# shield_passage_vitesse.net
KiCad netlist of a schematic drawn in EAGLE
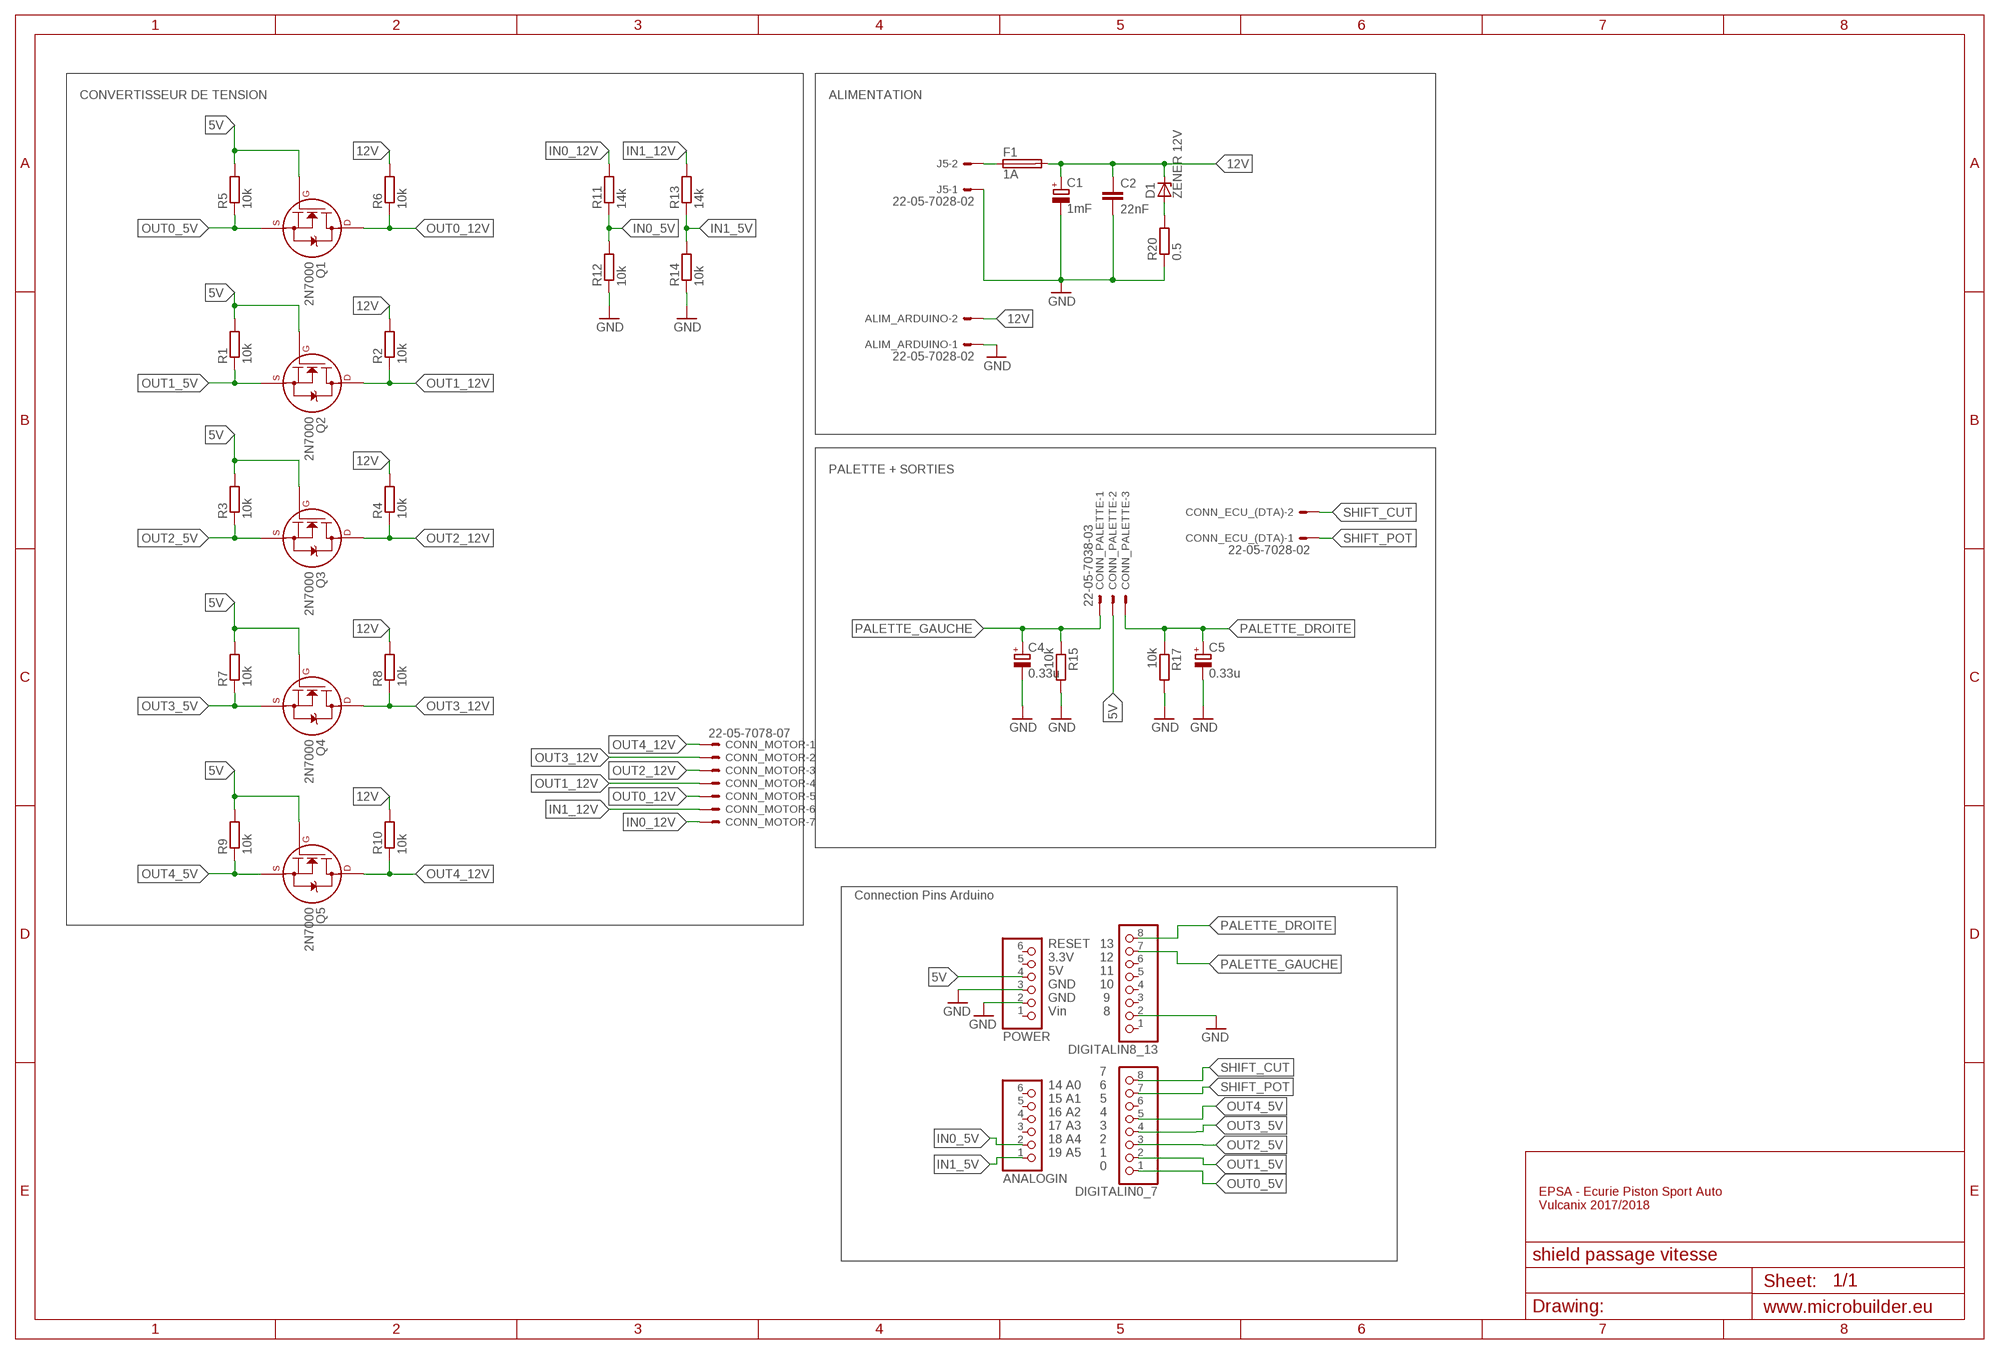
[diagram p0: schematic, sheet 1]

(export (version "E")
  (design (tool "Eeschema 10.0.6"))
  (components
    (comp (ref "ALIM_ARDUINO")
      (value "22-05-7028-02")
      (footprint "eagle-import:7395-02")
      (libsource (lib "eagle-import") (part "22-?-0205-7028"))
    )
    (comp (ref "ANALOGIN")
      (value "PINHD-1X6CB")
      (footprint "eagle-import:1X06-CLEANBIG")
      (libsource (lib "eagle-import") (part "PINHD-1X6CB"))
    )
    (comp (ref "C1")
      (value "1mF")
      (footprint "eagle-import:E7,5-16")
      (libsource (lib "eagle-import") (part "rcl_334_CPOL-EUE7.5-16"))
    )
    (comp (ref "C2")
      (value "22nF")
      (footprint "eagle-import:C025-025X050")
      (libsource (lib "eagle-import") (part "C-EU025-025X050"))
    )
    (comp (ref "C4")
      (value "0.33u")
      (footprint "eagle-import:E2,5-6E")
      (libsource (lib "eagle-import") (part "CPOL-EUE2,5-6E"))
    )
    (comp (ref "C5")
      (value "0.33u")
      (footprint "eagle-import:E2,5-6E")
      (libsource (lib "eagle-import") (part "CPOL-EUE2,5-6E"))
    )
    (comp (ref "CONN_ECU_(DTA)")
      (value "22-05-7028-02")
      (footprint "eagle-import:7395-02")
      (libsource (lib "eagle-import") (part "22-?-0205-7028"))
    )
    (comp (ref "CONN_MOTOR")
      (value "22-05-7078-07")
      (footprint "eagle-import:7395-07")
      (libsource (lib "eagle-import") (part "22-?-0705-7078"))
    )
    (comp (ref "CONN_PALETTE")
      (value "22-05-7038-03")
      (footprint "eagle-import:7395-03")
      (libsource (lib "eagle-import") (part "22-?-0305-7038"))
    )
    (comp (ref "D1")
      (value "ZENER 12V")
      (footprint "eagle-import:DO41Z10")
      (libsource (lib "eagle-import") (part "ZENER-DIODEDO41Z10"))
    )
    (comp (ref "DIGITALIN0_7")
      (value "PINHD-1X8CLEANBIG")
      (footprint "eagle-import:1X08-CLEANBIG")
      (libsource (lib "eagle-import") (part "PINHD-1X8CLEANBIG"))
    )
    (comp (ref "DIGITALIN8_13")
      (value "PINHD-1X8CLEANBIG")
      (footprint "eagle-import:1X08-CLEANBIG")
      (libsource (lib "eagle-import") (part "PINHD-1X8CLEANBIG"))
    )
    (comp (ref "F1")
      (value "1A")
      (footprint "eagle-import:SH25")
      (fields (field (name "MF") "SCHURTER") (field (name "MPN") "0031.8211"))
      (libsource (lib "eagle-import") (part "SH25"))
    )
    (comp (ref "J5")
      (value "22-05-7028-02")
      (footprint "eagle-import:7395-02")
      (libsource (lib "eagle-import") (part "22-?-0205-7028"))
    )
    (comp (ref "POWER")
      (value "PINHD-1X6CB")
      (footprint "eagle-import:1X06-CLEANBIG")
      (libsource (lib "eagle-import") (part "PINHD-1X6CB"))
    )
    (comp (ref "Q1")
      (value "2N7000")
      (footprint "eagle-import:TO-92")
      (libsource (lib "eagle-import") (part "2N700_TO920"))
    )
    (comp (ref "Q2")
      (value "2N7000")
      (footprint "eagle-import:TO-92")
      (libsource (lib "eagle-import") (part "2N700_TO920"))
    )
    (comp (ref "Q3")
      (value "2N7000")
      (footprint "eagle-import:TO-92")
      (libsource (lib "eagle-import") (part "2N700_TO920"))
    )
    (comp (ref "Q4")
      (value "2N7000")
      (footprint "eagle-import:TO-92")
      (libsource (lib "eagle-import") (part "2N700_TO920"))
    )
    (comp (ref "Q5")
      (value "2N7000")
      (footprint "eagle-import:TO-92")
      (libsource (lib "eagle-import") (part "2N700_TO920"))
    )
    (comp (ref "R1")
      (value "10k")
      (footprint "eagle-import:0204_7")
      (libsource (lib "eagle-import") (part "R-EU_0204/7"))
    )
    (comp (ref "R2")
      (value "10k")
      (footprint "eagle-import:0204_7")
      (libsource (lib "eagle-import") (part "R-EU_0204/7"))
    )
    (comp (ref "R3")
      (value "10k")
      (footprint "eagle-import:0204_7")
      (libsource (lib "eagle-import") (part "R-EU_0204/7"))
    )
    (comp (ref "R4")
      (value "10k")
      (footprint "eagle-import:0204_7")
      (libsource (lib "eagle-import") (part "R-EU_0204/7"))
    )
    (comp (ref "R5")
      (value "10k")
      (footprint "eagle-import:0204_7")
      (libsource (lib "eagle-import") (part "R-EU_0204/7"))
    )
    (comp (ref "R6")
      (value "10k")
      (footprint "eagle-import:0204_7")
      (libsource (lib "eagle-import") (part "R-EU_0204/7"))
    )
    (comp (ref "R7")
      (value "10k")
      (footprint "eagle-import:0204_7")
      (libsource (lib "eagle-import") (part "R-EU_0204/7"))
    )
    (comp (ref "R8")
      (value "10k")
      (footprint "eagle-import:0204_7")
      (libsource (lib "eagle-import") (part "R-EU_0204/7"))
    )
    (comp (ref "R9")
      (value "10k")
      (footprint "eagle-import:0204_7")
      (libsource (lib "eagle-import") (part "R-EU_0204/7"))
    )
    (comp (ref "R10")
      (value "10k")
      (footprint "eagle-import:0204_7")
      (libsource (lib "eagle-import") (part "R-EU_0204/7"))
    )
    (comp (ref "R11")
      (value "14k")
      (footprint "eagle-import:0204_7")
      (libsource (lib "eagle-import") (part "R-EU_0204/7"))
    )
    (comp (ref "R12")
      (value "10k")
      (footprint "eagle-import:0204_7")
      (libsource (lib "eagle-import") (part "R-EU_0204/7"))
    )
    (comp (ref "R13")
      (value "14k")
      (footprint "eagle-import:0204_7")
      (libsource (lib "eagle-import") (part "R-EU_0204/7"))
    )
    (comp (ref "R14")
      (value "10k")
      (footprint "eagle-import:0204_7")
      (libsource (lib "eagle-import") (part "R-EU_0204/7"))
    )
    (comp (ref "R15")
      (value "10k")
      (footprint "eagle-import:0204_7")
      (libsource (lib "eagle-import") (part "R-EU_0204/7"))
    )
    (comp (ref "R17")
      (value "10k")
      (footprint "eagle-import:0204_7")
      (libsource (lib "eagle-import") (part "R-EU_0204/7"))
    )
    (comp (ref "R20")
      (value "0.5")
      (footprint "eagle-import:0309_12")
      (libsource (lib "eagle-import") (part "R-EU_0309/12"))
    )
  )
  (nets
    (net (code "1") (name "5V") (class "Default")
      (node (ref "CONN_PALETTE") (pin "2") (pinfunction "S_2") (pintype "passive"))
      (node (ref "POWER") (pin "4") (pinfunction "4_4") (pintype "passive"))
      (node (ref "Q1") (pin "2") (pinfunction "G_2") (pintype "tri_state"))
      (node (ref "Q2") (pin "2") (pinfunction "G_2") (pintype "tri_state"))
      (node (ref "Q3") (pin "2") (pinfunction "G_2") (pintype "tri_state"))
      (node (ref "Q4") (pin "2") (pinfunction "G_2") (pintype "tri_state"))
      (node (ref "Q5") (pin "2") (pinfunction "G_2") (pintype "tri_state"))
      (node (ref "R1") (pin "2") (pinfunction "2_2") (pintype "passive"))
      (node (ref "R3") (pin "2") (pinfunction "2_2") (pintype "passive"))
      (node (ref "R5") (pin "2") (pinfunction "2_2") (pintype "passive"))
      (node (ref "R7") (pin "2") (pinfunction "2_2") (pintype "passive"))
      (node (ref "R9") (pin "2") (pinfunction "2_2") (pintype "passive"))
    )
    (net (code "2") (name "12V") (class "Default")
      (node (ref "ALIM_ARDUINO") (pin "2") (pinfunction "S_2") (pintype "passive"))
      (node (ref "C1") (pin "+") (pinfunction "+_+") (pintype "passive"))
      (node (ref "C2") (pin "1") (pinfunction "1_1") (pintype "passive"))
      (node (ref "D1") (pin "C") (pinfunction "C_C") (pintype "passive"))
      (node (ref "F1") (pin "2") (pinfunction "2_2") (pintype "passive"))
      (node (ref "R10") (pin "2") (pinfunction "2_2") (pintype "passive"))
      (node (ref "R2") (pin "2") (pinfunction "2_2") (pintype "passive"))
      (node (ref "R4") (pin "2") (pinfunction "2_2") (pintype "passive"))
      (node (ref "R6") (pin "2") (pinfunction "2_2") (pintype "passive"))
      (node (ref "R8") (pin "2") (pinfunction "2_2") (pintype "passive"))
    )
    (net (code "3") (name "GND") (class "Default")
      (node (ref "ALIM_ARDUINO") (pin "1") (pinfunction "S_1") (pintype "passive"))
      (node (ref "C1") (pin "-") (pinfunction "-_-") (pintype "passive"))
      (node (ref "C2") (pin "2") (pinfunction "2_2") (pintype "passive"))
      (node (ref "C4") (pin "-") (pinfunction "-_-") (pintype "passive"))
      (node (ref "C5") (pin "-") (pinfunction "-_-") (pintype "passive"))
      (node (ref "DIGITALIN8_13") (pin "2") (pinfunction "2_2") (pintype "passive"))
      (node (ref "J5") (pin "1") (pinfunction "S_1") (pintype "passive"))
      (node (ref "POWER") (pin "2") (pinfunction "2_2") (pintype "passive"))
      (node (ref "POWER") (pin "3") (pinfunction "3_3") (pintype "passive"))
      (node (ref "R12") (pin "1") (pinfunction "1_1") (pintype "passive"))
      (node (ref "R14") (pin "1") (pinfunction "1_1") (pintype "passive"))
      (node (ref "R15") (pin "2") (pinfunction "2_2") (pintype "passive"))
      (node (ref "R17") (pin "2") (pinfunction "2_2") (pintype "passive"))
      (node (ref "R20") (pin "1") (pinfunction "1_1") (pintype "passive"))
    )
    (net (code "4") (name "IN0_5V") (class "Default")
      (node (ref "ANALOGIN") (pin "2") (pinfunction "2_2") (pintype "passive"))
      (node (ref "R11") (pin "1") (pinfunction "1_1") (pintype "passive"))
      (node (ref "R12") (pin "2") (pinfunction "2_2") (pintype "passive"))
    )
    (net (code "5") (name "IN0_12V") (class "Default")
      (node (ref "CONN_MOTOR") (pin "7") (pinfunction "S_7") (pintype "passive"))
      (node (ref "R11") (pin "2") (pinfunction "2_2") (pintype "passive"))
    )
    (net (code "6") (name "IN1_5V") (class "Default")
      (node (ref "ANALOGIN") (pin "1") (pinfunction "1_1") (pintype "passive"))
      (node (ref "R13") (pin "1") (pinfunction "1_1") (pintype "passive"))
      (node (ref "R14") (pin "2") (pinfunction "2_2") (pintype "passive"))
    )
    (net (code "7") (name "IN1_12V") (class "Default")
      (node (ref "CONN_MOTOR") (pin "6") (pinfunction "S_6") (pintype "passive"))
      (node (ref "R13") (pin "2") (pinfunction "2_2") (pintype "passive"))
    )
    (net (code "8") (name "Net-(D1-PadA)") (class "Default")
      (node (ref "D1") (pin "A") (pinfunction "A_A") (pintype "passive"))
      (node (ref "R20") (pin "2") (pinfunction "2_2") (pintype "passive"))
    )
    (net (code "9") (name "Net-(J5B-S)") (class "Default")
      (node (ref "F1") (pin "1") (pinfunction "1_1") (pintype "passive"))
      (node (ref "J5") (pin "2") (pinfunction "S_2") (pintype "passive"))
    )
    (net (code "10") (name "OUT0_5V") (class "Default")
      (node (ref "DIGITALIN0_7") (pin "1") (pinfunction "1_1") (pintype "passive"))
      (node (ref "Q1") (pin "1") (pinfunction "S_1") (pintype "bidirectional"))
      (node (ref "R5") (pin "1") (pinfunction "1_1") (pintype "passive"))
    )
    (net (code "11") (name "OUT0_12V") (class "Default")
      (node (ref "CONN_MOTOR") (pin "5") (pinfunction "S_5") (pintype "passive"))
      (node (ref "Q1") (pin "3") (pinfunction "D_3") (pintype "bidirectional"))
      (node (ref "R6") (pin "1") (pinfunction "1_1") (pintype "passive"))
    )
    (net (code "12") (name "OUT1_5V") (class "Default")
      (node (ref "DIGITALIN0_7") (pin "2") (pinfunction "2_2") (pintype "passive"))
      (node (ref "Q2") (pin "1") (pinfunction "S_1") (pintype "bidirectional"))
      (node (ref "R1") (pin "1") (pinfunction "1_1") (pintype "passive"))
    )
    (net (code "13") (name "OUT1_12V") (class "Default")
      (node (ref "CONN_MOTOR") (pin "4") (pinfunction "S_4") (pintype "passive"))
      (node (ref "Q2") (pin "3") (pinfunction "D_3") (pintype "bidirectional"))
      (node (ref "R2") (pin "1") (pinfunction "1_1") (pintype "passive"))
    )
    (net (code "14") (name "OUT2_5V") (class "Default")
      (node (ref "DIGITALIN0_7") (pin "3") (pinfunction "3_3") (pintype "passive"))
      (node (ref "Q3") (pin "1") (pinfunction "S_1") (pintype "bidirectional"))
      (node (ref "R3") (pin "1") (pinfunction "1_1") (pintype "passive"))
    )
    (net (code "15") (name "OUT2_12V") (class "Default")
      (node (ref "CONN_MOTOR") (pin "3") (pinfunction "S_3") (pintype "passive"))
      (node (ref "Q3") (pin "3") (pinfunction "D_3") (pintype "bidirectional"))
      (node (ref "R4") (pin "1") (pinfunction "1_1") (pintype "passive"))
    )
    (net (code "16") (name "OUT3_5V") (class "Default")
      (node (ref "DIGITALIN0_7") (pin "4") (pinfunction "4_4") (pintype "passive"))
      (node (ref "Q4") (pin "1") (pinfunction "S_1") (pintype "bidirectional"))
      (node (ref "R7") (pin "1") (pinfunction "1_1") (pintype "passive"))
    )
    (net (code "17") (name "OUT3_12V") (class "Default")
      (node (ref "CONN_MOTOR") (pin "2") (pinfunction "S_2") (pintype "passive"))
      (node (ref "Q4") (pin "3") (pinfunction "D_3") (pintype "bidirectional"))
      (node (ref "R8") (pin "1") (pinfunction "1_1") (pintype "passive"))
    )
    (net (code "18") (name "OUT4_5V") (class "Default")
      (node (ref "DIGITALIN0_7") (pin "5") (pinfunction "5_5") (pintype "passive"))
      (node (ref "Q5") (pin "1") (pinfunction "S_1") (pintype "bidirectional"))
      (node (ref "R9") (pin "1") (pinfunction "1_1") (pintype "passive"))
    )
    (net (code "19") (name "OUT4_12V") (class "Default")
      (node (ref "CONN_MOTOR") (pin "1") (pinfunction "S_1") (pintype "passive"))
      (node (ref "Q5") (pin "3") (pinfunction "D_3") (pintype "bidirectional"))
      (node (ref "R10") (pin "1") (pinfunction "1_1") (pintype "passive"))
    )
    (net (code "20") (name "PALETTE_DROITE") (class "Default")
      (node (ref "C5") (pin "+") (pinfunction "+_+") (pintype "passive"))
      (node (ref "CONN_PALETTE") (pin "3") (pinfunction "S_3") (pintype "passive"))
      (node (ref "DIGITALIN8_13") (pin "8") (pinfunction "8_8") (pintype "passive"))
      (node (ref "R17") (pin "1") (pinfunction "1_1") (pintype "passive"))
    )
    (net (code "21") (name "PALETTE_GAUCHE") (class "Default")
      (node (ref "C4") (pin "+") (pinfunction "+_+") (pintype "passive"))
      (node (ref "CONN_PALETTE") (pin "1") (pinfunction "S_1") (pintype "passive"))
      (node (ref "DIGITALIN8_13") (pin "7") (pinfunction "7_7") (pintype "passive"))
      (node (ref "R15") (pin "1") (pinfunction "1_1") (pintype "passive"))
    )
    (net (code "22") (name "SHIFT_CUT") (class "Default")
      (node (ref "CONN_ECU_(DTA)") (pin "2") (pinfunction "S_2") (pintype "passive"))
      (node (ref "DIGITALIN0_7") (pin "8") (pinfunction "8_8") (pintype "passive"))
    )
    (net (code "23") (name "SHIFT_POT") (class "Default")
      (node (ref "CONN_ECU_(DTA)") (pin "1") (pinfunction "S_1") (pintype "passive"))
      (node (ref "DIGITALIN0_7") (pin "7") (pinfunction "7_7") (pintype "passive"))
    )
    (net (code "24") (name "unconnected-(ANALOGIN-Pad3)") (class "Default")
      (node (ref "ANALOGIN") (pin "3") (pinfunction "3_3") (pintype "passive"))
    )
    (net (code "25") (name "unconnected-(ANALOGIN-Pad4)") (class "Default")
      (node (ref "ANALOGIN") (pin "4") (pinfunction "4_4") (pintype "passive"))
    )
    (net (code "26") (name "unconnected-(ANALOGIN-Pad5)") (class "Default")
      (node (ref "ANALOGIN") (pin "5") (pinfunction "5_5") (pintype "passive"))
    )
    (net (code "27") (name "unconnected-(ANALOGIN-Pad6)") (class "Default")
      (node (ref "ANALOGIN") (pin "6") (pinfunction "6_6") (pintype "passive"))
    )
    (net (code "28") (name "unconnected-(DIGITALIN0_7-Pad6)") (class "Default")
      (node (ref "DIGITALIN0_7") (pin "6") (pinfunction "6_6") (pintype "passive"))
    )
    (net (code "29") (name "unconnected-(DIGITALIN8_13-Pad1)") (class "Default")
      (node (ref "DIGITALIN8_13") (pin "1") (pinfunction "1_1") (pintype "passive"))
    )
    (net (code "30") (name "unconnected-(DIGITALIN8_13-Pad3)") (class "Default")
      (node (ref "DIGITALIN8_13") (pin "3") (pinfunction "3_3") (pintype "passive"))
    )
    (net (code "31") (name "unconnected-(DIGITALIN8_13-Pad4)") (class "Default")
      (node (ref "DIGITALIN8_13") (pin "4") (pinfunction "4_4") (pintype "passive"))
    )
    (net (code "32") (name "unconnected-(DIGITALIN8_13-Pad5)") (class "Default")
      (node (ref "DIGITALIN8_13") (pin "5") (pinfunction "5_5") (pintype "passive"))
    )
    (net (code "33") (name "unconnected-(DIGITALIN8_13-Pad6)") (class "Default")
      (node (ref "DIGITALIN8_13") (pin "6") (pinfunction "6_6") (pintype "passive"))
    )
    (net (code "34") (name "unconnected-(POWER-Pad1)") (class "Default")
      (node (ref "POWER") (pin "1") (pinfunction "1_1") (pintype "passive"))
    )
    (net (code "35") (name "unconnected-(POWER-Pad5)") (class "Default")
      (node (ref "POWER") (pin "5") (pinfunction "5_5") (pintype "passive"))
    )
    (net (code "36") (name "unconnected-(POWER-Pad6)") (class "Default")
      (node (ref "POWER") (pin "6") (pinfunction "6_6") (pintype "passive"))
    )
  )
)
